# drv.net
KiCad netlist of a schematic drawn in Altium Designer
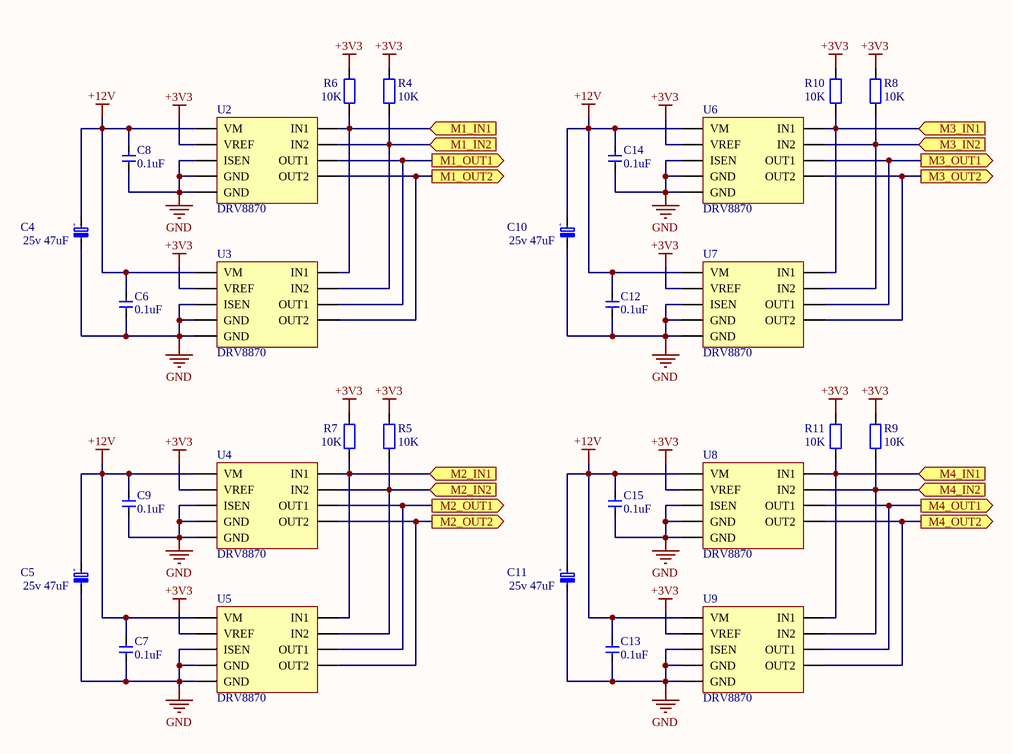
[diagram p0: drv.SchDoc]

(export (version "E")
  (design (tool "Eeschema 10.0.6"))
  (components
    (comp (ref "C4")
      (value "25v 47uF")
      (footprint "CAP_TANT_D")
      (description "Tantal SMD Cap")
      (libsource (lib "Asterisk") (part "CAP Tantal"))
    )
    (comp (ref "C5")
      (value "25v 47uF")
      (footprint "CAP_TANT_D")
      (description "Tantal SMD Cap")
      (libsource (lib "Asterisk") (part "CAP Tantal"))
    )
    (comp (ref "C6")
      (value "0.1uF")
      (footprint "CAP0805")
      (description "Ceramic SMD Cap")
      (libsource (lib "Asterisk") (part "CAP Ceramic"))
    )
    (comp (ref "C7")
      (value "0.1uF")
      (footprint "CAP0805")
      (description "Ceramic SMD Cap")
      (libsource (lib "Asterisk") (part "CAP Ceramic"))
    )
    (comp (ref "C8")
      (value "0.1uF")
      (footprint "CAP0805")
      (description "Ceramic SMD Cap")
      (libsource (lib "Asterisk") (part "CAP Ceramic"))
    )
    (comp (ref "C9")
      (value "0.1uF")
      (footprint "CAP0805")
      (description "Ceramic SMD Cap")
      (libsource (lib "Asterisk") (part "CAP Ceramic"))
    )
    (comp (ref "C10")
      (value "25v 47uF")
      (footprint "CAP_TANT_D")
      (description "Tantal SMD Cap")
      (libsource (lib "Asterisk") (part "CAP Tantal"))
    )
    (comp (ref "C11")
      (value "25v 47uF")
      (footprint "CAP_TANT_D")
      (description "Tantal SMD Cap")
      (libsource (lib "Asterisk") (part "CAP Tantal"))
    )
    (comp (ref "C12")
      (value "0.1uF")
      (footprint "CAP0805")
      (description "Ceramic SMD Cap")
      (libsource (lib "Asterisk") (part "CAP Ceramic"))
    )
    (comp (ref "C13")
      (value "0.1uF")
      (footprint "CAP0805")
      (description "Ceramic SMD Cap")
      (libsource (lib "Asterisk") (part "CAP Ceramic"))
    )
    (comp (ref "C14")
      (value "0.1uF")
      (footprint "CAP0805")
      (description "Ceramic SMD Cap")
      (libsource (lib "Asterisk") (part "CAP Ceramic"))
    )
    (comp (ref "C15")
      (value "0.1uF")
      (footprint "CAP0805")
      (description "Ceramic SMD Cap")
      (libsource (lib "Asterisk") (part "CAP Ceramic"))
    )
    (comp (ref "R4")
      (value "10K")
      (footprint "RES0805")
      (description "RES smd")
      (libsource (lib "Asterisk") (part "RES"))
    )
    (comp (ref "R5")
      (value "10K")
      (footprint "RES0805")
      (description "RES smd")
      (libsource (lib "Asterisk") (part "RES"))
    )
    (comp (ref "R6")
      (value "10K")
      (footprint "RES0805")
      (description "RES smd")
      (libsource (lib "Asterisk") (part "RES"))
    )
    (comp (ref "R7")
      (value "10K")
      (footprint "RES0805")
      (description "RES smd")
      (libsource (lib "Asterisk") (part "RES"))
    )
    (comp (ref "R8")
      (value "10K")
      (footprint "RES0805")
      (description "RES smd")
      (libsource (lib "Asterisk") (part "RES"))
    )
    (comp (ref "R9")
      (value "10K")
      (footprint "RES0805")
      (description "RES smd")
      (libsource (lib "Asterisk") (part "RES"))
    )
    (comp (ref "R10")
      (value "10K")
      (footprint "RES0805")
      (description "RES smd")
      (libsource (lib "Asterisk") (part "RES"))
    )
    (comp (ref "R11")
      (value "10K")
      (footprint "RES0805")
      (description "RES smd")
      (libsource (lib "Asterisk") (part "RES"))
    )
    (comp (ref "U2")
      (value "DRV8870")
      (footprint "DRV8870")
      (description "DC motor driver 3.6A")
      (libsource (lib "Asterisk") (part "DRV8870"))
    )
    (comp (ref "U3")
      (value "DRV8870")
      (footprint "DRV8870")
      (description "DC motor driver 3.6A")
      (libsource (lib "Asterisk") (part "DRV8870"))
    )
    (comp (ref "U4")
      (value "DRV8870")
      (footprint "DRV8870")
      (description "DC motor driver 3.6A")
      (libsource (lib "Asterisk") (part "DRV8870"))
    )
    (comp (ref "U5")
      (value "DRV8870")
      (footprint "DRV8870")
      (description "DC motor driver 3.6A")
      (libsource (lib "Asterisk") (part "DRV8870"))
    )
    (comp (ref "U6")
      (value "DRV8870")
      (footprint "DRV8870")
      (description "DC motor driver 3.6A")
      (libsource (lib "Asterisk") (part "DRV8870"))
    )
    (comp (ref "U7")
      (value "DRV8870")
      (footprint "DRV8870")
      (description "DC motor driver 3.6A")
      (libsource (lib "Asterisk") (part "DRV8870"))
    )
    (comp (ref "U8")
      (value "DRV8870")
      (footprint "DRV8870")
      (description "DC motor driver 3.6A")
      (libsource (lib "Asterisk") (part "DRV8870"))
    )
    (comp (ref "U9")
      (value "DRV8870")
      (footprint "DRV8870")
      (description "DC motor driver 3.6A")
      (libsource (lib "Asterisk") (part "DRV8870"))
    )
  )
  (nets
    (net (code "1") (name "+3V3") (class "Default")
      (node (ref "R10") (pin "2") (pinfunction "2_2") (pintype "passive"))
      (node (ref "R11") (pin "2") (pinfunction "2_2") (pintype "passive"))
      (node (ref "R4") (pin "2") (pinfunction "2_2") (pintype "passive"))
      (node (ref "R5") (pin "2") (pinfunction "2_2") (pintype "passive"))
      (node (ref "R6") (pin "2") (pinfunction "2_2") (pintype "passive"))
      (node (ref "R7") (pin "2") (pinfunction "2_2") (pintype "passive"))
      (node (ref "R8") (pin "2") (pinfunction "2_2") (pintype "passive"))
      (node (ref "R9") (pin "2") (pinfunction "2_2") (pintype "passive"))
      (node (ref "U2") (pin "4") (pinfunction "VREF_4") (pintype "passive"))
      (node (ref "U3") (pin "4") (pinfunction "VREF_4") (pintype "passive"))
      (node (ref "U4") (pin "4") (pinfunction "VREF_4") (pintype "passive"))
      (node (ref "U5") (pin "4") (pinfunction "VREF_4") (pintype "passive"))
      (node (ref "U6") (pin "4") (pinfunction "VREF_4") (pintype "passive"))
      (node (ref "U7") (pin "4") (pinfunction "VREF_4") (pintype "passive"))
      (node (ref "U8") (pin "4") (pinfunction "VREF_4") (pintype "passive"))
      (node (ref "U9") (pin "4") (pinfunction "VREF_4") (pintype "passive"))
    )
    (net (code "2") (name "+12V") (class "Default")
      (node (ref "C10") (pin "2") (pinfunction "PLUS_2") (pintype "passive"))
      (node (ref "C11") (pin "2") (pinfunction "PLUS_2") (pintype "passive"))
      (node (ref "C12") (pin "2") (pinfunction "2_2") (pintype "passive"))
      (node (ref "C13") (pin "2") (pinfunction "2_2") (pintype "passive"))
      (node (ref "C14") (pin "2") (pinfunction "2_2") (pintype "passive"))
      (node (ref "C15") (pin "2") (pinfunction "2_2") (pintype "passive"))
      (node (ref "C4") (pin "2") (pinfunction "PLUS_2") (pintype "passive"))
      (node (ref "C5") (pin "2") (pinfunction "PLUS_2") (pintype "passive"))
      (node (ref "C6") (pin "2") (pinfunction "2_2") (pintype "passive"))
      (node (ref "C7") (pin "2") (pinfunction "2_2") (pintype "passive"))
      (node (ref "C8") (pin "2") (pinfunction "2_2") (pintype "passive"))
      (node (ref "C9") (pin "2") (pinfunction "2_2") (pintype "passive"))
      (node (ref "U2") (pin "5") (pinfunction "VM_5") (pintype "passive"))
      (node (ref "U3") (pin "5") (pinfunction "VM_5") (pintype "passive"))
      (node (ref "U4") (pin "5") (pinfunction "VM_5") (pintype "passive"))
      (node (ref "U5") (pin "5") (pinfunction "VM_5") (pintype "passive"))
      (node (ref "U6") (pin "5") (pinfunction "VM_5") (pintype "passive"))
      (node (ref "U7") (pin "5") (pinfunction "VM_5") (pintype "passive"))
      (node (ref "U8") (pin "5") (pinfunction "VM_5") (pintype "passive"))
      (node (ref "U9") (pin "5") (pinfunction "VM_5") (pintype "passive"))
    )
    (net (code "3") (name "/M1_IN1") (class "Default")
      (node (ref "R6") (pin "1") (pinfunction "1_1") (pintype "passive"))
      (node (ref "U2") (pin "3") (pinfunction "IN1_3") (pintype "passive"))
      (node (ref "U3") (pin "3") (pinfunction "IN1_3") (pintype "passive"))
    )
    (net (code "4") (name "/M1_IN2") (class "Default")
      (node (ref "R4") (pin "1") (pinfunction "1_1") (pintype "passive"))
      (node (ref "U2") (pin "2") (pinfunction "IN2_2") (pintype "passive"))
      (node (ref "U3") (pin "2") (pinfunction "IN2_2") (pintype "passive"))
    )
    (net (code "5") (name "/M1_OUT1") (class "Default")
      (node (ref "U2") (pin "6") (pinfunction "OUT1_6") (pintype "passive"))
      (node (ref "U3") (pin "6") (pinfunction "OUT1_6") (pintype "passive"))
    )
    (net (code "6") (name "/M1_OUT2") (class "Default")
      (node (ref "U2") (pin "8") (pinfunction "OUT2_8") (pintype "passive"))
      (node (ref "U3") (pin "8") (pinfunction "OUT2_8") (pintype "passive"))
    )
    (net (code "7") (name "/M2_IN1") (class "Default")
      (node (ref "R7") (pin "1") (pinfunction "1_1") (pintype "passive"))
      (node (ref "U4") (pin "3") (pinfunction "IN1_3") (pintype "passive"))
      (node (ref "U5") (pin "3") (pinfunction "IN1_3") (pintype "passive"))
    )
    (net (code "8") (name "/M2_IN2") (class "Default")
      (node (ref "R5") (pin "1") (pinfunction "1_1") (pintype "passive"))
      (node (ref "U4") (pin "2") (pinfunction "IN2_2") (pintype "passive"))
      (node (ref "U5") (pin "2") (pinfunction "IN2_2") (pintype "passive"))
    )
    (net (code "9") (name "/M2_OUT1") (class "Default")
      (node (ref "U4") (pin "6") (pinfunction "OUT1_6") (pintype "passive"))
      (node (ref "U5") (pin "6") (pinfunction "OUT1_6") (pintype "passive"))
    )
    (net (code "10") (name "/M2_OUT2") (class "Default")
      (node (ref "U4") (pin "8") (pinfunction "OUT2_8") (pintype "passive"))
      (node (ref "U5") (pin "8") (pinfunction "OUT2_8") (pintype "passive"))
    )
    (net (code "11") (name "/M3_IN1") (class "Default")
      (node (ref "R10") (pin "1") (pinfunction "1_1") (pintype "passive"))
      (node (ref "U6") (pin "3") (pinfunction "IN1_3") (pintype "passive"))
      (node (ref "U7") (pin "3") (pinfunction "IN1_3") (pintype "passive"))
    )
    (net (code "12") (name "/M3_IN2") (class "Default")
      (node (ref "R8") (pin "1") (pinfunction "1_1") (pintype "passive"))
      (node (ref "U6") (pin "2") (pinfunction "IN2_2") (pintype "passive"))
      (node (ref "U7") (pin "2") (pinfunction "IN2_2") (pintype "passive"))
    )
    (net (code "13") (name "/M3_OUT1") (class "Default")
      (node (ref "U6") (pin "6") (pinfunction "OUT1_6") (pintype "passive"))
      (node (ref "U7") (pin "6") (pinfunction "OUT1_6") (pintype "passive"))
    )
    (net (code "14") (name "/M3_OUT2") (class "Default")
      (node (ref "U6") (pin "8") (pinfunction "OUT2_8") (pintype "passive"))
      (node (ref "U7") (pin "8") (pinfunction "OUT2_8") (pintype "passive"))
    )
    (net (code "15") (name "/M4_IN1") (class "Default")
      (node (ref "R11") (pin "1") (pinfunction "1_1") (pintype "passive"))
      (node (ref "U8") (pin "3") (pinfunction "IN1_3") (pintype "passive"))
      (node (ref "U9") (pin "3") (pinfunction "IN1_3") (pintype "passive"))
    )
    (net (code "16") (name "/M4_IN2") (class "Default")
      (node (ref "R9") (pin "1") (pinfunction "1_1") (pintype "passive"))
      (node (ref "U8") (pin "2") (pinfunction "IN2_2") (pintype "passive"))
      (node (ref "U9") (pin "2") (pinfunction "IN2_2") (pintype "passive"))
    )
    (net (code "17") (name "/M4_OUT1") (class "Default")
      (node (ref "U8") (pin "6") (pinfunction "OUT1_6") (pintype "passive"))
      (node (ref "U9") (pin "6") (pinfunction "OUT1_6") (pintype "passive"))
    )
    (net (code "18") (name "/M4_OUT2") (class "Default")
      (node (ref "U8") (pin "8") (pinfunction "OUT2_8") (pintype "passive"))
      (node (ref "U9") (pin "8") (pinfunction "OUT2_8") (pintype "passive"))
    )
    (net (code "19") (name "GND") (class "Default")
      (node (ref "C10") (pin "1") (pinfunction "MINUS_1") (pintype "passive"))
      (node (ref "C11") (pin "1") (pinfunction "MINUS_1") (pintype "passive"))
      (node (ref "C12") (pin "1") (pinfunction "1_1") (pintype "passive"))
      (node (ref "C13") (pin "1") (pinfunction "1_1") (pintype "passive"))
      (node (ref "C14") (pin "1") (pinfunction "1_1") (pintype "passive"))
      (node (ref "C15") (pin "1") (pinfunction "1_1") (pintype "passive"))
      (node (ref "C4") (pin "1") (pinfunction "MINUS_1") (pintype "passive"))
      (node (ref "C5") (pin "1") (pinfunction "MINUS_1") (pintype "passive"))
      (node (ref "C6") (pin "1") (pinfunction "1_1") (pintype "passive"))
      (node (ref "C7") (pin "1") (pinfunction "1_1") (pintype "passive"))
      (node (ref "C8") (pin "1") (pinfunction "1_1") (pintype "passive"))
      (node (ref "C9") (pin "1") (pinfunction "1_1") (pintype "passive"))
      (node (ref "U2") (pin "1") (pinfunction "GND_1") (pintype "passive"))
      (node (ref "U2") (pin "7") (pinfunction "ISEN_7") (pintype "passive"))
      (node (ref "U2") (pin "9") (pinfunction "GND_9") (pintype "passive"))
      (node (ref "U3") (pin "1") (pinfunction "GND_1") (pintype "passive"))
      (node (ref "U3") (pin "7") (pinfunction "ISEN_7") (pintype "passive"))
      (node (ref "U3") (pin "9") (pinfunction "GND_9") (pintype "passive"))
      (node (ref "U4") (pin "1") (pinfunction "GND_1") (pintype "passive"))
      (node (ref "U4") (pin "7") (pinfunction "ISEN_7") (pintype "passive"))
      (node (ref "U4") (pin "9") (pinfunction "GND_9") (pintype "passive"))
      (node (ref "U5") (pin "1") (pinfunction "GND_1") (pintype "passive"))
      (node (ref "U5") (pin "7") (pinfunction "ISEN_7") (pintype "passive"))
      (node (ref "U5") (pin "9") (pinfunction "GND_9") (pintype "passive"))
      (node (ref "U6") (pin "1") (pinfunction "GND_1") (pintype "passive"))
      (node (ref "U6") (pin "7") (pinfunction "ISEN_7") (pintype "passive"))
      (node (ref "U6") (pin "9") (pinfunction "GND_9") (pintype "passive"))
      (node (ref "U7") (pin "1") (pinfunction "GND_1") (pintype "passive"))
      (node (ref "U7") (pin "7") (pinfunction "ISEN_7") (pintype "passive"))
      (node (ref "U7") (pin "9") (pinfunction "GND_9") (pintype "passive"))
      (node (ref "U8") (pin "1") (pinfunction "GND_1") (pintype "passive"))
      (node (ref "U8") (pin "7") (pinfunction "ISEN_7") (pintype "passive"))
      (node (ref "U8") (pin "9") (pinfunction "GND_9") (pintype "passive"))
      (node (ref "U9") (pin "1") (pinfunction "GND_1") (pintype "passive"))
      (node (ref "U9") (pin "7") (pinfunction "ISEN_7") (pintype "passive"))
      (node (ref "U9") (pin "9") (pinfunction "GND_9") (pintype "passive"))
    )
  )
)
